# MCU.net
KiCad netlist of a schematic drawn in Altium Designer
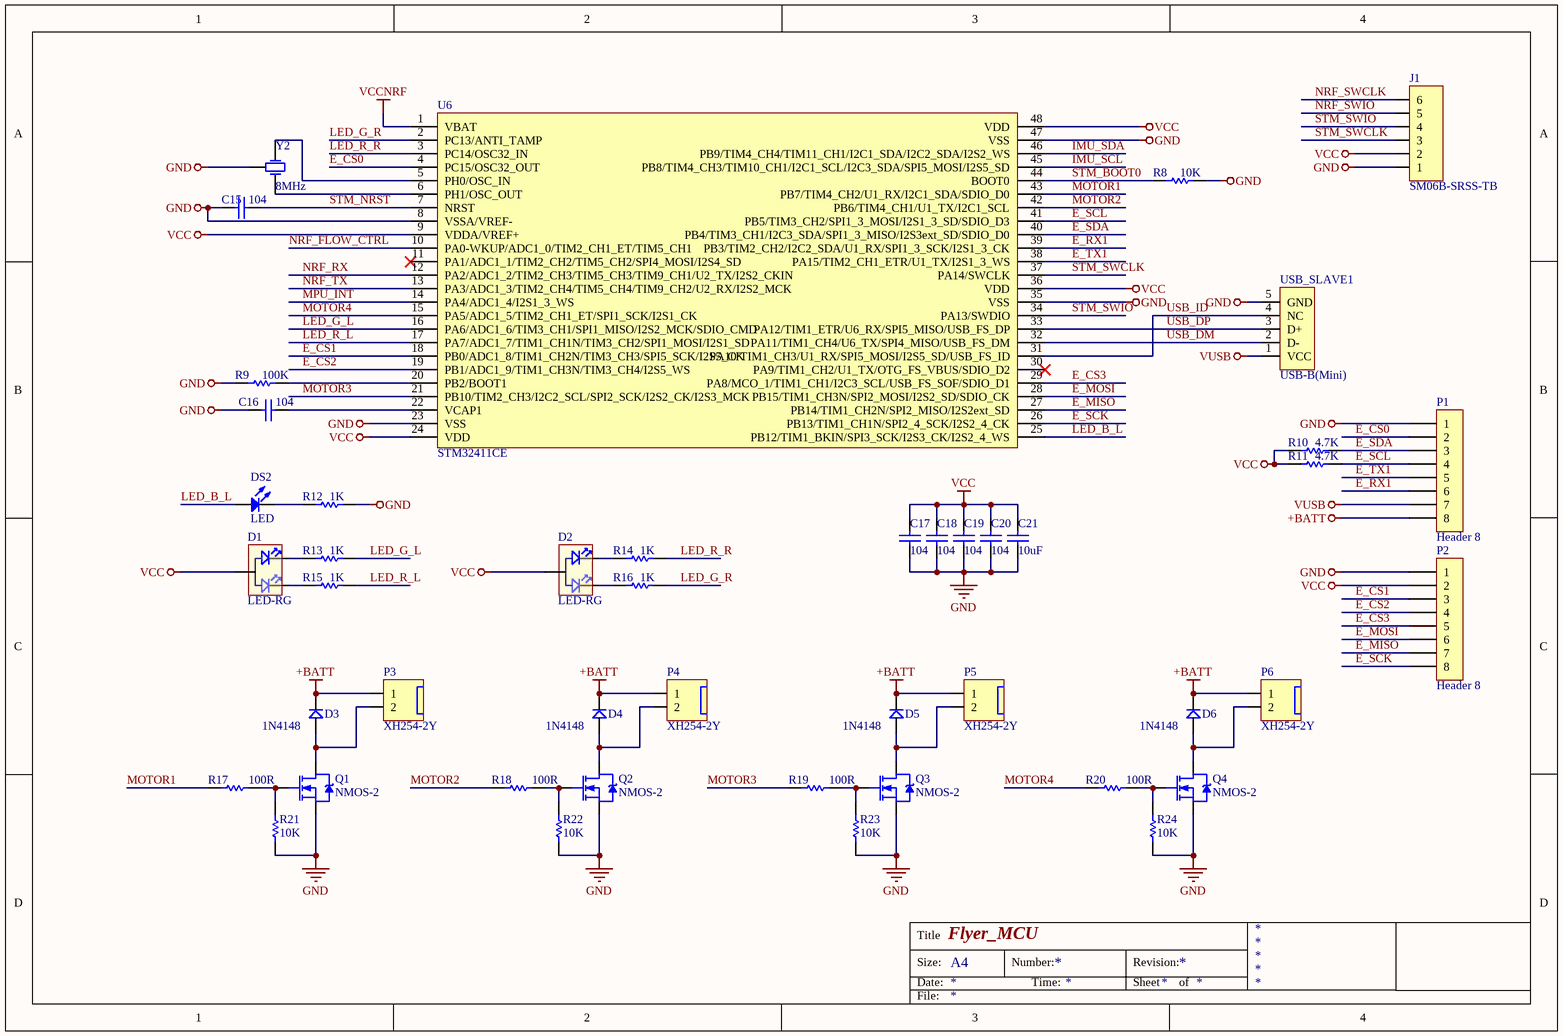
[diagram p0: MCU.SchDoc]

(export (version "E")
  (design (tool "Eeschema 10.0.6"))
  (components
    (comp (ref "C15")
      (value "104")
      (footprint "C0603")
      (description "电容")
      (fields (field (name "PUBLISHER") "Altium Limited"))
      (libsource (lib "Devices") (part "C0603"))
    )
    (comp (ref "C16")
      (value "104")
      (footprint "C0603")
      (description "电容")
      (fields (field (name "PUBLISHER") "Altium Limited"))
      (libsource (lib "Devices") (part "C0603"))
    )
    (comp (ref "C17")
      (value "104")
      (footprint "C0603")
      (description "电容")
      (fields (field (name "PUBLISHER") "Altium Limited"))
      (libsource (lib "Devices") (part "C0603"))
    )
    (comp (ref "C18")
      (value "104")
      (footprint "C0603")
      (description "电容")
      (fields (field (name "PUBLISHER") "Altium Limited"))
      (libsource (lib "Devices") (part "C0603"))
    )
    (comp (ref "C19")
      (value "104")
      (footprint "C0603")
      (description "电容")
      (fields (field (name "PUBLISHER") "Altium Limited"))
      (libsource (lib "Devices") (part "C0603"))
    )
    (comp (ref "C20")
      (value "104")
      (footprint "C0603")
      (description "电容")
      (fields (field (name "PUBLISHER") "Altium Limited"))
      (libsource (lib "Devices") (part "C0603"))
    )
    (comp (ref "C21")
      (value "10uF")
      (footprint "C0603")
      (description "电容")
      (fields (field (name "PUBLISHER") "Altium Limited"))
      (libsource (lib "Devices") (part "C0603"))
    )
    (comp (ref "D1")
      (value "LED-RG")
      (footprint "LED-2-1206")
      (description "LED 1206 侧贴 双色")
      (libsource (lib "Devices") (part "LED-2"))
    )
    (comp (ref "D2")
      (value "LED-RG")
      (footprint "LED-2-1206")
      (description "LED 1206 侧贴 双色")
      (libsource (lib "Devices") (part "LED-2"))
    )
    (comp (ref "D3")
      (value "1N4148")
      (footprint "SOD-523")
      (description "通用二极管")
      (libsource (lib "Devices") (part "D"))
    )
    (comp (ref "D4")
      (value "1N4148")
      (footprint "SOD-523")
      (description "通用二极管")
      (libsource (lib "Devices") (part "D"))
    )
    (comp (ref "D5")
      (value "1N4148")
      (footprint "SOD-523")
      (description "通用二极管")
      (libsource (lib "Devices") (part "D"))
    )
    (comp (ref "D6")
      (value "1N4148")
      (footprint "SOD-523")
      (description "通用二极管")
      (libsource (lib "Devices") (part "D"))
    )
    (comp (ref "DS2")
      (value "LED")
      (footprint "LED-2-1206")
      (description "Typical RED, GREEN, YELLOW, AMBER GaAs LED")
      (fields (field (name "PUBLISHER") "Altium Limited"))
      (libsource (lib "Devices") (part "LED"))
    )
    (comp (ref "J1")
      (value "SM06B-SRSS-TB")
      (footprint "SM06B-SRSS-TB")
      (libsource (lib "Connectors") (part "SM06B-SRSS-TB"))
    )
    (comp (ref "P1")
      (value "Header 8")
      (footprint "HDR1X8")
      (description "Header, 8-Pin")
      (fields (field (name "PUBLISHER") "Altium Limited"))
      (libsource (lib "Connectors") (part "Header 8"))
    )
    (comp (ref "P2")
      (value "Header 8")
      (footprint "HDR1X8")
      (description "Header, 8-Pin")
      (fields (field (name "PUBLISHER") "Altium Limited"))
      (libsource (lib "Connectors") (part "Header 8"))
    )
    (comp (ref "P3")
      (value "XH254-2Y")
      (footprint "XH-AW-125-2Y")
      (fields (field (name "PUBLISHER") "Altium Limited"))
      (libsource (lib "Connectors") (part "XH254-2Y"))
    )
    (comp (ref "P4")
      (value "XH254-2Y")
      (footprint "XH-AW-125-2Y")
      (fields (field (name "PUBLISHER") "Altium Limited"))
      (libsource (lib "Connectors") (part "XH254-2Y"))
    )
    (comp (ref "P5")
      (value "XH254-2Y")
      (footprint "XH-AW-125-2Y")
      (fields (field (name "PUBLISHER") "Altium Limited"))
      (libsource (lib "Connectors") (part "XH254-2Y"))
    )
    (comp (ref "P6")
      (value "XH254-2Y")
      (footprint "XH-AW-125-2Y")
      (fields (field (name "PUBLISHER") "Altium Limited"))
      (libsource (lib "Connectors") (part "XH254-2Y"))
    )
    (comp (ref "Q1")
      (value "NMOS-2")
      (footprint "SOT-23-3L")
      (description "N-Channel Power MOSFET")
      (fields (field (name "PUBLISHER") "Altium Limited"))
      (libsource (lib "Devices") (part "NMOS-2"))
    )
    (comp (ref "Q2")
      (value "NMOS-2")
      (footprint "SOT-23-3L")
      (description "N-Channel Power MOSFET")
      (fields (field (name "PUBLISHER") "Altium Limited"))
      (libsource (lib "Devices") (part "NMOS-2"))
    )
    (comp (ref "Q3")
      (value "NMOS-2")
      (footprint "SOT-23-3L")
      (description "N-Channel Power MOSFET")
      (fields (field (name "PUBLISHER") "Altium Limited"))
      (libsource (lib "Devices") (part "NMOS-2"))
    )
    (comp (ref "Q4")
      (value "NMOS-2")
      (footprint "SOT-23-3L")
      (description "N-Channel Power MOSFET")
      (fields (field (name "PUBLISHER") "Altium Limited"))
      (libsource (lib "Devices") (part "NMOS-2"))
    )
    (comp (ref "R8")
      (value "10K")
      (footprint "R0603")
      (description "电阻")
      (fields (field (name "PUBLISHER") "Altium Limited"))
      (libsource (lib "Devices") (part "RES0603"))
    )
    (comp (ref "R9")
      (value "100K")
      (footprint "R0603")
      (description "电阻")
      (fields (field (name "PUBLISHER") "Altium Limited"))
      (libsource (lib "Devices") (part "RES0603"))
    )
    (comp (ref "R10")
      (value "4.7K")
      (footprint "R0603")
      (description "电阻")
      (fields (field (name "PUBLISHER") "Altium Limited"))
      (libsource (lib "Devices") (part "RES0603"))
    )
    (comp (ref "R11")
      (value "4.7K")
      (footprint "R0603")
      (description "电阻")
      (fields (field (name "PUBLISHER") "Altium Limited"))
      (libsource (lib "Devices") (part "RES0603"))
    )
    (comp (ref "R12")
      (value "1K")
      (footprint "R0603")
      (description "电阻")
      (fields (field (name "PUBLISHER") "Altium Limited"))
      (libsource (lib "Devices") (part "RES0603"))
    )
    (comp (ref "R13")
      (value "1K")
      (footprint "R0603")
      (description "电阻")
      (fields (field (name "PUBLISHER") "Altium Limited"))
      (libsource (lib "Devices") (part "RES0603"))
    )
    (comp (ref "R14")
      (value "1K")
      (footprint "R0603")
      (description "电阻")
      (fields (field (name "PUBLISHER") "Altium Limited"))
      (libsource (lib "Devices") (part "RES0603"))
    )
    (comp (ref "R15")
      (value "1K")
      (footprint "R0603")
      (description "电阻")
      (fields (field (name "PUBLISHER") "Altium Limited"))
      (libsource (lib "Devices") (part "RES0603"))
    )
    (comp (ref "R16")
      (value "1K")
      (footprint "R0603")
      (description "电阻")
      (fields (field (name "PUBLISHER") "Altium Limited"))
      (libsource (lib "Devices") (part "RES0603"))
    )
    (comp (ref "R17")
      (value "100R")
      (footprint "R0603")
      (description "电阻")
      (fields (field (name "PUBLISHER") "Altium Limited"))
      (libsource (lib "Devices") (part "RES0603"))
    )
    (comp (ref "R18")
      (value "100R")
      (footprint "R0603")
      (description "电阻")
      (fields (field (name "PUBLISHER") "Altium Limited"))
      (libsource (lib "Devices") (part "RES0603"))
    )
    (comp (ref "R19")
      (value "100R")
      (footprint "R0603")
      (description "电阻")
      (fields (field (name "PUBLISHER") "Altium Limited"))
      (libsource (lib "Devices") (part "RES0603"))
    )
    (comp (ref "R20")
      (value "100R")
      (footprint "R0603")
      (description "电阻")
      (fields (field (name "PUBLISHER") "Altium Limited"))
      (libsource (lib "Devices") (part "RES0603"))
    )
    (comp (ref "R21")
      (value "10K")
      (footprint "R0603")
      (description "电阻")
      (fields (field (name "PUBLISHER") "Altium Limited"))
      (libsource (lib "Devices") (part "RES0603"))
    )
    (comp (ref "R22")
      (value "10K")
      (footprint "R0603")
      (description "电阻")
      (fields (field (name "PUBLISHER") "Altium Limited"))
      (libsource (lib "Devices") (part "RES0603"))
    )
    (comp (ref "R23")
      (value "10K")
      (footprint "R0603")
      (description "电阻")
      (fields (field (name "PUBLISHER") "Altium Limited"))
      (libsource (lib "Devices") (part "RES0603"))
    )
    (comp (ref "R24")
      (value "10K")
      (footprint "R0603")
      (description "电阻")
      (fields (field (name "PUBLISHER") "Altium Limited"))
      (libsource (lib "Devices") (part "RES0603"))
    )
    (comp (ref "U6")
      (value "STM32411CE")
      (footprint "UFQFPN48")
      (description "STM32411xC_xE")
      (libsource (lib "IC") (part "STM32F411xC"))
    )
    (comp (ref "USB_SLAVE1")
      (value "USB-B(Mini)")
      (footprint "USB-MicroUSB")
      (libsource (lib "Connectors") (part "USB5"))
    )
    (comp (ref "Y2")
      (value "8MHz")
      (footprint "X-CSTCE")
      (description "Crystal Oscillator")
      (fields (field (name "PUBLISHER") "Altium Limited"))
      (libsource (lib "Devices") (part "XTAL_2"))
    )
  )
  (nets
    (net (code "1") (name "+BATT") (class "Default")
      (node (ref "D3") (pin "2") (pintype "passive"))
      (node (ref "D4") (pin "2") (pintype "passive"))
      (node (ref "D5") (pin "2") (pintype "passive"))
      (node (ref "D6") (pin "2") (pintype "passive"))
      (node (ref "P1") (pin "8") (pinfunction "8_8") (pintype "passive"))
      (node (ref "P3") (pin "1") (pinfunction "1_1") (pintype "passive"))
      (node (ref "P4") (pin "1") (pinfunction "1_1") (pintype "passive"))
      (node (ref "P5") (pin "1") (pinfunction "1_1") (pintype "passive"))
      (node (ref "P6") (pin "1") (pinfunction "1_1") (pintype "passive"))
    )
    (net (code "2") (name "/E_CS0") (class "Default")
      (node (ref "P1") (pin "2") (pinfunction "2_2") (pintype "passive"))
      (node (ref "U6") (pin "4") (pinfunction "PC15/OSC32_OUT_4") (pintype "passive"))
    )
    (net (code "3") (name "/E_CS1") (class "Default")
      (node (ref "P2") (pin "3") (pinfunction "3_3") (pintype "passive"))
      (node (ref "U6") (pin "18") (pinfunction "PB0/ADC1_8/TIM1_CH2N/TIM3_CH3/SPI5_SCK/I2S5_CK_18") (pintype "passive"))
    )
    (net (code "4") (name "/E_CS2") (class "Default")
      (node (ref "P2") (pin "4") (pinfunction "4_4") (pintype "passive"))
      (node (ref "U6") (pin "19") (pinfunction "PB1/ADC1_9/TIM1_CH3N/TIM3_CH4/I2S5_WS_19") (pintype "passive"))
    )
    (net (code "5") (name "/E_CS3") (class "Default")
      (node (ref "P2") (pin "5") (pinfunction "5_5") (pintype "passive"))
      (node (ref "U6") (pin "29") (pinfunction "PA8/MCO_1/TIM1_CH1/I2C3_SCL/USB_FS_SOF/SDIO_D1_29") (pintype "passive"))
    )
    (net (code "6") (name "/E_MISO") (class "Default")
      (node (ref "P2") (pin "7") (pinfunction "7_7") (pintype "passive"))
      (node (ref "U6") (pin "27") (pinfunction "PB14/TIM1_CH2N/SPI2_MISO/I2S2ext_SD_27") (pintype "passive"))
    )
    (net (code "7") (name "/E_MOSI") (class "Default")
      (node (ref "P2") (pin "6") (pinfunction "6_6") (pintype "passive"))
      (node (ref "U6") (pin "28") (pinfunction "PB15/TIM1_CH3N/SPI2_MOSI/I2S2_SD/SDIO_CK_28") (pintype "passive"))
    )
    (net (code "8") (name "/E_RX1") (class "Default")
      (node (ref "P1") (pin "6") (pinfunction "6_6") (pintype "passive"))
      (node (ref "U6") (pin "39") (pinfunction "PB3/TIM2_CH2/I2C2_SDA/U1_RX/SPI1_3_SCK/I2S1_3_CK_39") (pintype "passive"))
    )
    (net (code "9") (name "/E_SCK") (class "Default")
      (node (ref "P2") (pin "8") (pinfunction "8_8") (pintype "passive"))
      (node (ref "U6") (pin "26") (pinfunction "PB13/TIM1_CH1N/SPI2_4_SCK/I2S2_4_CK_26") (pintype "passive"))
    )
    (net (code "10") (name "/E_SCL") (class "Default")
      (node (ref "P1") (pin "4") (pinfunction "4_4") (pintype "passive"))
      (node (ref "R11") (pin "1") (pinfunction "1_1") (pintype "passive"))
      (node (ref "U6") (pin "41") (pinfunction "PB5/TIM3_CH2/SPI1_3_MOSI/I2S1_3_SD/SDIO_D3_41") (pintype "passive"))
    )
    (net (code "11") (name "/E_SDA") (class "Default")
      (node (ref "P1") (pin "3") (pinfunction "3_3") (pintype "passive"))
      (node (ref "R10") (pin "1") (pinfunction "1_1") (pintype "passive"))
      (node (ref "U6") (pin "40") (pinfunction "PB4/TIM3_CH1/I2C3_SDA/SPI1_3_MISO/I2S3ext_SD/SDIO_D0_40") (pintype "passive"))
    )
    (net (code "12") (name "/E_TX1") (class "Default")
      (node (ref "P1") (pin "5") (pinfunction "5_5") (pintype "passive"))
      (node (ref "U6") (pin "38") (pinfunction "PA15/TIM2_CH1_ETR/U1_TX/I2S1_3_WS_38") (pintype "passive"))
    )
    (net (code "13") (name "/IMU_SCL") (class "Default")
      (node (ref "U6") (pin "45") (pinfunction "PB8/TIM4_CH3/TIM10_CH1/I2C1_SCL/I2C3_SDA/SPI5_MOSI/I2S5_SD_45") (pintype "passive"))
    )
    (net (code "14") (name "/IMU_SDA") (class "Default")
      (node (ref "U6") (pin "46") (pinfunction "PB9/TIM4_CH4/TIM11_CH1/I2C1_SDA/I2C2_SDA/I2S2_WS_46") (pintype "passive"))
    )
    (net (code "15") (name "/LED_B_L") (class "Default")
      (node (ref "DS2") (pin "1") (pinfunction "A_1") (pintype "passive"))
      (node (ref "U6") (pin "25") (pinfunction "PB12/TIM1_BKIN/SPI3_SCK/I2S3_CK/I2S2_4_WS_25") (pintype "passive"))
    )
    (net (code "16") (name "/LED_G_L") (class "Default")
      (node (ref "R13") (pin "1") (pinfunction "1_1") (pintype "passive"))
      (node (ref "U6") (pin "16") (pinfunction "PA6/ADC1_6/TIM3_CH1/SPI1_MISO/I2S2_MCK/SDIO_CMD_16") (pintype "passive"))
    )
    (net (code "17") (name "/LED_G_R") (class "Default")
      (node (ref "R16") (pin "1") (pinfunction "1_1") (pintype "passive"))
      (node (ref "U6") (pin "2") (pinfunction "PC13/ANTI_TAMP_2") (pintype "passive"))
    )
    (net (code "18") (name "/LED_R_L") (class "Default")
      (node (ref "R15") (pin "1") (pinfunction "1_1") (pintype "passive"))
      (node (ref "U6") (pin "17") (pinfunction "PA7/ADC1_7/TIM1_CH1N/TIM3_CH2/SPI1_MOSI/I2S1_SD_17") (pintype "passive"))
    )
    (net (code "19") (name "/LED_R_R") (class "Default")
      (node (ref "R14") (pin "1") (pinfunction "1_1") (pintype "passive"))
      (node (ref "U6") (pin "3") (pinfunction "PC14/OSC32_IN_3") (pintype "passive"))
    )
    (net (code "20") (name "/MOTOR1") (class "Default")
      (node (ref "R17") (pin "1") (pinfunction "1_1") (pintype "passive"))
      (node (ref "U6") (pin "43") (pinfunction "PB7/TIM4_CH2/U1_RX/I2C1_SDA/SDIO_D0_43") (pintype "passive"))
    )
    (net (code "21") (name "/MOTOR2") (class "Default")
      (node (ref "R18") (pin "1") (pinfunction "1_1") (pintype "passive"))
      (node (ref "U6") (pin "42") (pinfunction "PB6/TIM4_CH1/U1_TX/I2C1_SCL_42") (pintype "passive"))
    )
    (net (code "22") (name "/MOTOR3") (class "Default")
      (node (ref "R19") (pin "1") (pinfunction "1_1") (pintype "passive"))
      (node (ref "U6") (pin "21") (pinfunction "PB10/TIM2_CH3/I2C2_SCL/SPI2_SCK/I2S2_CK/I2S3_MCK_21") (pintype "passive"))
    )
    (net (code "23") (name "/MOTOR4") (class "Default")
      (node (ref "R20") (pin "1") (pinfunction "1_1") (pintype "passive"))
      (node (ref "U6") (pin "15") (pinfunction "PA5/ADC1_5/TIM2_CH1_ET/SPI1_SCK/I2S1_CK_15") (pintype "passive"))
    )
    (net (code "24") (name "/MPU_INT") (class "Default")
      (node (ref "U6") (pin "14") (pinfunction "PA4/ADC1_4/I2S1_3_WS_14") (pintype "passive"))
    )
    (net (code "25") (name "/NRF_FLOW_CTRL") (class "Default")
      (node (ref "U6") (pin "10") (pinfunction "PA0-WKUP/ADC1_0/TIM2_CH1_ET/TIM5_CH1_10") (pintype "passive"))
    )
    (net (code "26") (name "/NRF_RX") (class "Default")
      (node (ref "U6") (pin "12") (pinfunction "PA2/ADC1_2/TIM2_CH3/TIM5_CH3/TIM9_CH1/U2_TX/I2S2_CKIN_12") (pintype "passive"))
    )
    (net (code "27") (name "/NRF_SWCLK") (class "Default")
      (node (ref "J1") (pin "6") (pinfunction "6_6") (pintype "passive"))
    )
    (net (code "28") (name "/NRF_SWIO") (class "Default")
      (node (ref "J1") (pin "5") (pinfunction "5_5") (pintype "passive"))
    )
    (net (code "29") (name "/NRF_TX") (class "Default")
      (node (ref "U6") (pin "13") (pinfunction "PA3/ADC1_3/TIM2_CH4/TIM5_CH4/TIM9_CH2/U2_RX/I2S2_MCK_13") (pintype "passive"))
    )
    (net (code "30") (name "/STM_BOOT0") (class "Default")
      (node (ref "R8") (pin "2") (pinfunction "2_2") (pintype "passive"))
      (node (ref "U6") (pin "44") (pinfunction "BOOT0_44") (pintype "passive"))
    )
    (net (code "31") (name "/STM_NRST") (class "Default")
      (node (ref "C15") (pin "1") (pinfunction "1_1") (pintype "passive"))
      (node (ref "U6") (pin "7") (pinfunction "NRST_7") (pintype "passive"))
    )
    (net (code "32") (name "/STM_SWCLK") (class "Default")
      (node (ref "J1") (pin "3") (pinfunction "3_3") (pintype "passive"))
      (node (ref "U6") (pin "37") (pinfunction "PA14/SWCLK_37") (pintype "passive"))
    )
    (net (code "33") (name "/STM_SWIO") (class "Default")
      (node (ref "J1") (pin "4") (pinfunction "4_4") (pintype "passive"))
      (node (ref "U6") (pin "34") (pinfunction "PA13/SWDIO_34") (pintype "passive"))
    )
    (net (code "34") (name "/USB_DM") (class "Default")
      (node (ref "U6") (pin "32") (pinfunction "PA11/TIM1_CH4/U6_TX/SPI4_MISO/USB_FS_DM_32") (pintype "passive"))
      (node (ref "USB_SLAVE1") (pin "2") (pinfunction "D-_2") (pintype "passive"))
    )
    (net (code "35") (name "/USB_DP") (class "Default")
      (node (ref "U6") (pin "33") (pinfunction "PA12/TIM1_ETR/U6_RX/SPI5_MISO/USB_FS_DP_33") (pintype "passive"))
      (node (ref "USB_SLAVE1") (pin "3") (pinfunction "D+_3") (pintype "passive"))
    )
    (net (code "36") (name "/USB_ID") (class "Default")
      (node (ref "U6") (pin "31") (pinfunction "PA10/TIM1_CH3/U1_RX/SPI5_MOSI/I2S5_SD/USB_FS_ID_31") (pintype "passive"))
      (node (ref "USB_SLAVE1") (pin "4") (pinfunction "NC_4") (pintype "passive"))
    )
    (net (code "37") (name "GND") (class "Default")
      (node (ref "C15") (pin "2") (pinfunction "2_2") (pintype "passive"))
      (node (ref "C16") (pin "2") (pinfunction "2_2") (pintype "passive"))
      (node (ref "C17") (pin "1") (pinfunction "1_1") (pintype "passive"))
      (node (ref "C18") (pin "1") (pinfunction "1_1") (pintype "passive"))
      (node (ref "C19") (pin "1") (pinfunction "1_1") (pintype "passive"))
      (node (ref "C20") (pin "1") (pinfunction "1_1") (pintype "passive"))
      (node (ref "C21") (pin "1") (pinfunction "1_1") (pintype "passive"))
      (node (ref "J1") (pin "1") (pinfunction "1_1") (pintype "passive"))
      (node (ref "P1") (pin "1") (pinfunction "1_1") (pintype "passive"))
      (node (ref "P2") (pin "1") (pinfunction "1_1") (pintype "passive"))
      (node (ref "Q1") (pin "3") (pinfunction "S_3") (pintype "passive"))
      (node (ref "Q2") (pin "3") (pinfunction "S_3") (pintype "passive"))
      (node (ref "Q3") (pin "3") (pinfunction "S_3") (pintype "passive"))
      (node (ref "Q4") (pin "3") (pinfunction "S_3") (pintype "passive"))
      (node (ref "R12") (pin "1") (pinfunction "1_1") (pintype "passive"))
      (node (ref "R21") (pin "1") (pinfunction "1_1") (pintype "passive"))
      (node (ref "R22") (pin "1") (pinfunction "1_1") (pintype "passive"))
      (node (ref "R23") (pin "1") (pinfunction "1_1") (pintype "passive"))
      (node (ref "R24") (pin "1") (pinfunction "1_1") (pintype "passive"))
      (node (ref "R8") (pin "1") (pinfunction "1_1") (pintype "passive"))
      (node (ref "R9") (pin "2") (pinfunction "2_2") (pintype "passive"))
      (node (ref "U6") (pin "23") (pinfunction "VSS_23") (pintype "passive"))
      (node (ref "U6") (pin "35") (pinfunction "VSS_35") (pintype "passive"))
      (node (ref "U6") (pin "47") (pinfunction "VSS_47") (pintype "passive"))
      (node (ref "U6") (pin "8") (pinfunction "VSSA/VREF-_8") (pintype "passive"))
      (node (ref "USB_SLAVE1") (pin "5") (pinfunction "GND_5") (pintype "passive"))
      (node (ref "Y2") (pin "3") (pinfunction "3_3") (pintype "passive"))
    )
    (net (code "38") (name "Net-(D1-Pad2)") (class "Default")
      (node (ref "D1") (pin "2") (pinfunction "2_2") (pintype "passive"))
      (node (ref "R15") (pin "2") (pinfunction "2_2") (pintype "passive"))
    )
    (net (code "39") (name "Net-(D1-Pad3)") (class "Default")
      (node (ref "D1") (pin "3") (pinfunction "3_3") (pintype "passive"))
      (node (ref "R13") (pin "2") (pinfunction "2_2") (pintype "passive"))
    )
    (net (code "40") (name "Net-(D2-Pad2)") (class "Default")
      (node (ref "D2") (pin "2") (pinfunction "2_2") (pintype "passive"))
      (node (ref "R16") (pin "2") (pinfunction "2_2") (pintype "passive"))
    )
    (net (code "41") (name "Net-(D2-Pad3)") (class "Default")
      (node (ref "D2") (pin "3") (pinfunction "3_3") (pintype "passive"))
      (node (ref "R14") (pin "2") (pinfunction "2_2") (pintype "passive"))
    )
    (net (code "42") (name "Net-(DS2-K)") (class "Default")
      (node (ref "DS2") (pin "2") (pinfunction "K_2") (pintype "passive"))
      (node (ref "R12") (pin "2") (pinfunction "2_2") (pintype "passive"))
    )
    (net (code "43") (name "Net-(Q1-D)") (class "Default")
      (node (ref "D3") (pin "1") (pintype "passive"))
      (node (ref "P3") (pin "2") (pinfunction "2_2") (pintype "passive"))
      (node (ref "Q1") (pin "2") (pinfunction "D_2") (pintype "passive"))
    )
    (net (code "44") (name "Net-(Q1-G)") (class "Default")
      (node (ref "Q1") (pin "1") (pinfunction "G_1") (pintype "passive"))
      (node (ref "R17") (pin "2") (pinfunction "2_2") (pintype "passive"))
      (node (ref "R21") (pin "2") (pinfunction "2_2") (pintype "passive"))
    )
    (net (code "45") (name "Net-(Q2-D)") (class "Default")
      (node (ref "D4") (pin "1") (pintype "passive"))
      (node (ref "P4") (pin "2") (pinfunction "2_2") (pintype "passive"))
      (node (ref "Q2") (pin "2") (pinfunction "D_2") (pintype "passive"))
    )
    (net (code "46") (name "Net-(Q2-G)") (class "Default")
      (node (ref "Q2") (pin "1") (pinfunction "G_1") (pintype "passive"))
      (node (ref "R18") (pin "2") (pinfunction "2_2") (pintype "passive"))
      (node (ref "R22") (pin "2") (pinfunction "2_2") (pintype "passive"))
    )
    (net (code "47") (name "Net-(Q3-D)") (class "Default")
      (node (ref "D5") (pin "1") (pintype "passive"))
      (node (ref "P5") (pin "2") (pinfunction "2_2") (pintype "passive"))
      (node (ref "Q3") (pin "2") (pinfunction "D_2") (pintype "passive"))
    )
    (net (code "48") (name "Net-(Q3-G)") (class "Default")
      (node (ref "Q3") (pin "1") (pinfunction "G_1") (pintype "passive"))
      (node (ref "R19") (pin "2") (pinfunction "2_2") (pintype "passive"))
      (node (ref "R23") (pin "2") (pinfunction "2_2") (pintype "passive"))
    )
    (net (code "49") (name "Net-(Q4-D)") (class "Default")
      (node (ref "D6") (pin "1") (pintype "passive"))
      (node (ref "P6") (pin "2") (pinfunction "2_2") (pintype "passive"))
      (node (ref "Q4") (pin "2") (pinfunction "D_2") (pintype "passive"))
    )
    (net (code "50") (name "Net-(Q4-G)") (class "Default")
      (node (ref "Q4") (pin "1") (pinfunction "G_1") (pintype "passive"))
      (node (ref "R20") (pin "2") (pinfunction "2_2") (pintype "passive"))
      (node (ref "R24") (pin "2") (pinfunction "2_2") (pintype "passive"))
    )
    (net (code "51") (name "Net-(U6-PB2{slash}BOOT1)") (class "Default")
      (node (ref "R9") (pin "1") (pinfunction "1_1") (pintype "passive"))
      (node (ref "U6") (pin "20") (pinfunction "PB2/BOOT1_20") (pintype "passive"))
    )
    (net (code "52") (name "Net-(U6-PH0{slash}OSC_IN)") (class "Default")
      (node (ref "U6") (pin "5") (pinfunction "PH0/OSC_IN_5") (pintype "passive"))
      (node (ref "Y2") (pin "1") (pinfunction "OSC1_1") (pintype "passive"))
    )
    (net (code "53") (name "Net-(U6-PH1{slash}OSC_OUT)") (class "Default")
      (node (ref "U6") (pin "6") (pinfunction "PH1/OSC_OUT_6") (pintype "passive"))
      (node (ref "Y2") (pin "2") (pinfunction "OSC2_2") (pintype "passive"))
    )
    (net (code "54") (name "Net-(U6-VCAP1)") (class "Default")
      (node (ref "C16") (pin "1") (pinfunction "1_1") (pintype "passive"))
      (node (ref "U6") (pin "22") (pinfunction "VCAP1_22") (pintype "passive"))
    )
    (net (code "55") (name "VCC") (class "Default")
      (node (ref "C17") (pin "2") (pinfunction "2_2") (pintype "passive"))
      (node (ref "C18") (pin "2") (pinfunction "2_2") (pintype "passive"))
      (node (ref "C19") (pin "2") (pinfunction "2_2") (pintype "passive"))
      (node (ref "C20") (pin "2") (pinfunction "2_2") (pintype "passive"))
      (node (ref "C21") (pin "2") (pinfunction "2_2") (pintype "passive"))
      (node (ref "D1") (pin "1") (pinfunction "1_1") (pintype "passive"))
      (node (ref "D2") (pin "1") (pinfunction "1_1") (pintype "passive"))
      (node (ref "J1") (pin "2") (pinfunction "2_2") (pintype "passive"))
      (node (ref "P2") (pin "2") (pinfunction "2_2") (pintype "passive"))
      (node (ref "R10") (pin "2") (pinfunction "2_2") (pintype "passive"))
      (node (ref "R11") (pin "2") (pinfunction "2_2") (pintype "passive"))
      (node (ref "U6") (pin "24") (pinfunction "VDD_24") (pintype "passive"))
      (node (ref "U6") (pin "36") (pinfunction "VDD_36") (pintype "passive"))
      (node (ref "U6") (pin "48") (pinfunction "VDD_48") (pintype "passive"))
      (node (ref "U6") (pin "9") (pinfunction "VDDA/VREF+_9") (pintype "passive"))
    )
    (net (code "56") (name "VCCNRF") (class "Default")
      (node (ref "U6") (pin "1") (pinfunction "VBAT_1") (pintype "passive"))
    )
    (net (code "57") (name "VUSB") (class "Default")
      (node (ref "P1") (pin "7") (pinfunction "7_7") (pintype "passive"))
      (node (ref "USB_SLAVE1") (pin "1") (pinfunction "VCC_1") (pintype "passive"))
    )
    (net (code "58") (name "unconnected-(U6-PA1{slash}ADC1_1{slash}TIM2_CH2{slash}TIM5_CH2{slash}SPI4_MOSI{slash}I2S4_SD-Pad11)") (class "Default")
      (node (ref "U6") (pin "11") (pinfunction "PA1/ADC1_1/TIM2_CH2/TIM5_CH2/SPI4_MOSI/I2S4_SD_11") (pintype "passive+no_connect"))
    )
    (net (code "59") (name "unconnected-(U6-PA9{slash}TIM1_CH2{slash}U1_TX{slash}OTG_FS_VBUS{slash}SDIO_D2-Pad30)") (class "Default")
      (node (ref "U6") (pin "30") (pinfunction "PA9/TIM1_CH2/U1_TX/OTG_FS_VBUS/SDIO_D2_30") (pintype "passive+no_connect"))
    )
  )
)
